# Ethernet_Phy_4_esp32.net
KiCad netlist of a schematic drawn in EAGLE
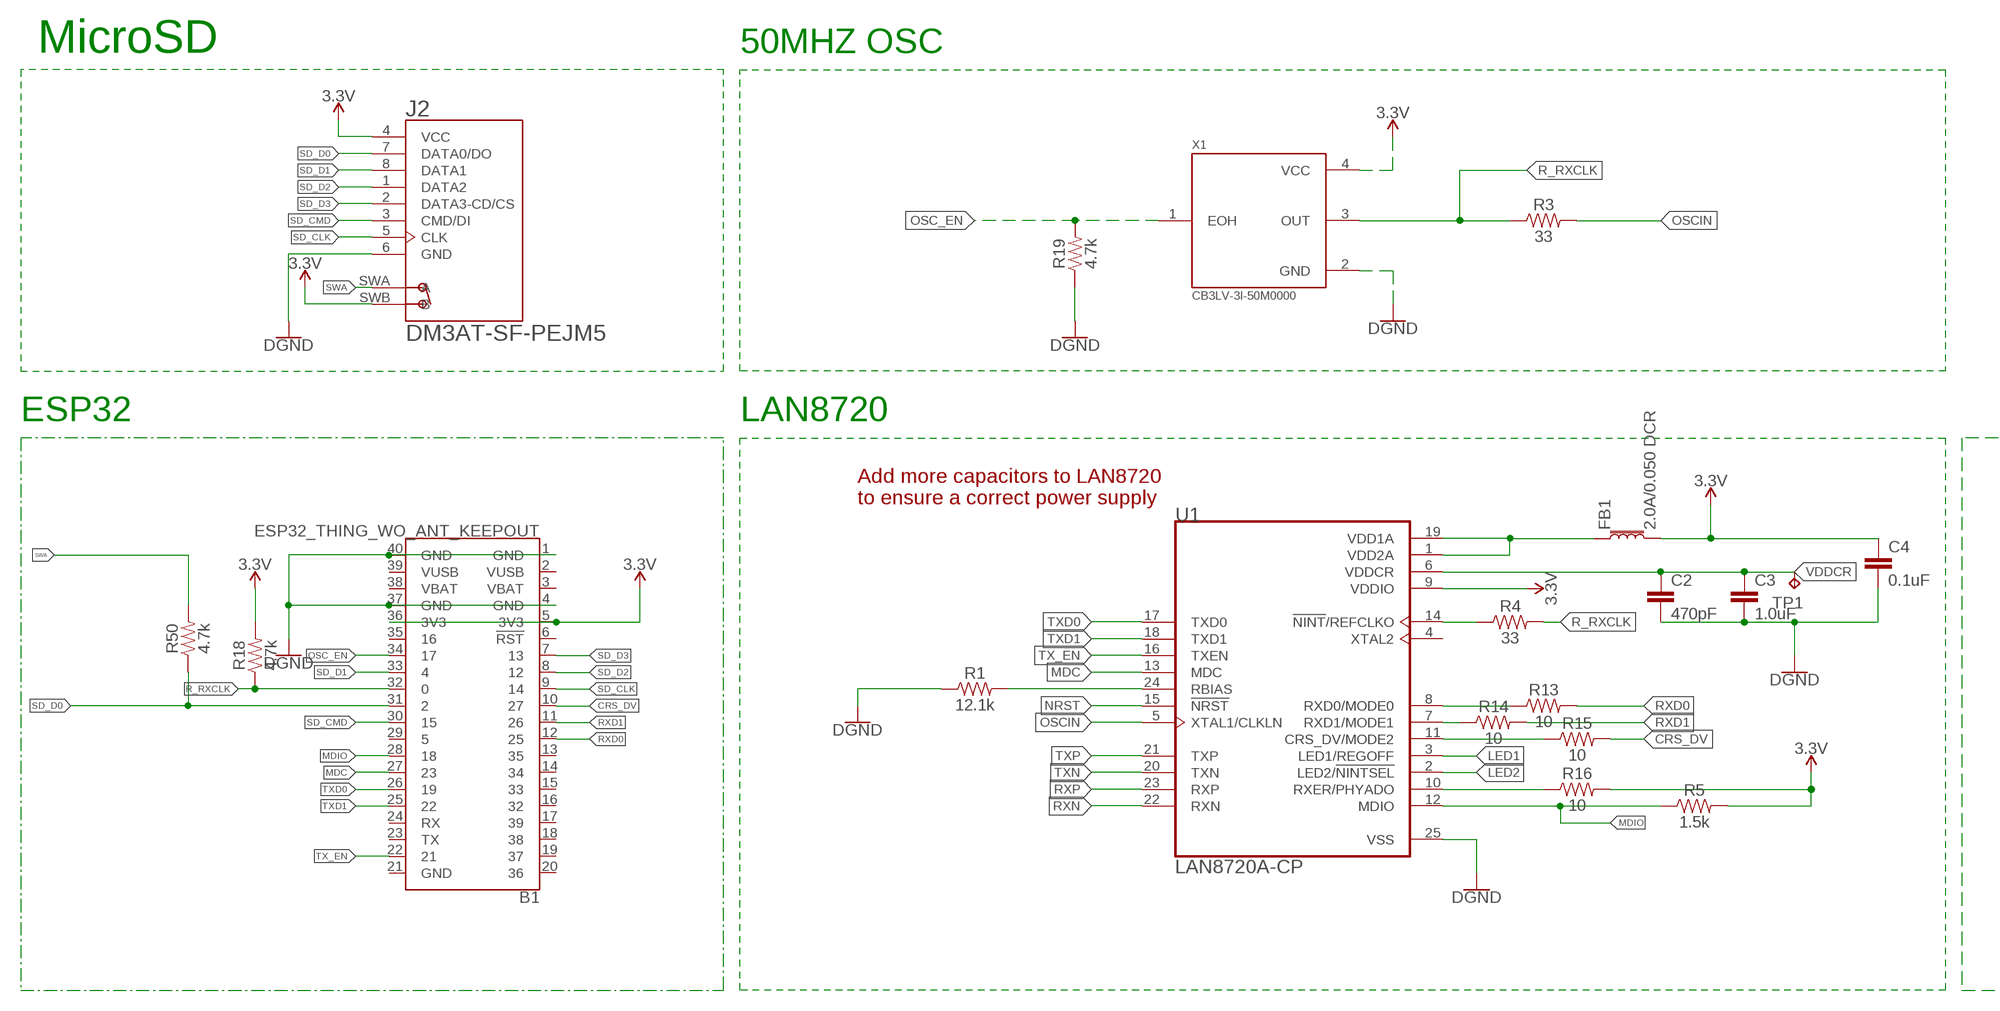
[diagram p0: schematic, sheet 1, part 1 of 2]
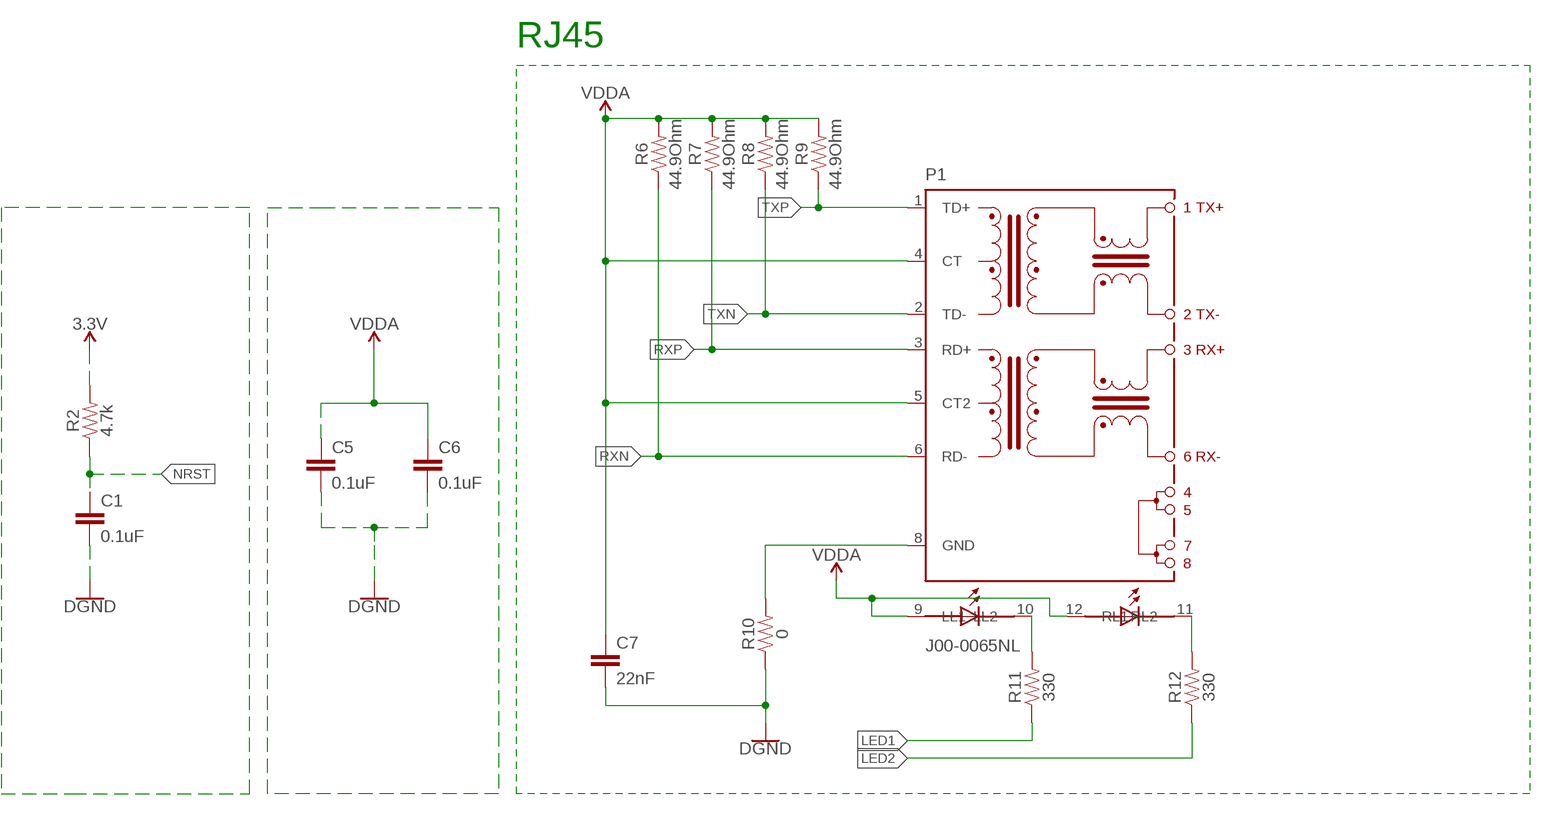
[diagram p1: schematic, sheet 1, part 2 of 2]

(export (version "E")
  (design (tool "Eeschema 10.0.6"))
  (components
    (comp (ref "B1")
      (value "ESP32_THING_WO_ANT_KEEPOUT")
      (footprint "eagle-import:ESP32_THING_NO_ANT")
      (libsource (lib "eagle-import") (part "ESP32_THING_WO_ANT_KEEPOUT"))
    )
    (comp (ref "C1")
      (value "0.1uF")
      (footprint "eagle-import:0603")
      (libsource (lib "eagle-import") (part "0.1UF-0603-100V-10%"))
    )
    (comp (ref "C2")
      (value "470pF")
      (footprint "eagle-import:0603")
      (libsource (lib "eagle-import") (part "470PF-0603-50V-5%"))
    )
    (comp (ref "C3")
      (value "1.0uF")
      (footprint "eagle-import:0603")
      (libsource (lib "eagle-import") (part "1.0UF-0603-16V-10%"))
    )
    (comp (ref "C4")
      (value "0.1uF")
      (footprint "eagle-import:0603")
      (libsource (lib "eagle-import") (part "0.1UF-0603-100V-10%"))
    )
    (comp (ref "C5")
      (value "0.1uF")
      (footprint "eagle-import:0603")
      (libsource (lib "eagle-import") (part "0.1UF-0603-25V-(+80/-20%)"))
    )
    (comp (ref "C6")
      (value "0.1uF")
      (footprint "eagle-import:0603")
      (libsource (lib "eagle-import") (part "0.1UF-0603-25V-(+80/-20%)"))
    )
    (comp (ref "C7")
      (value "22nF")
      (footprint "eagle-import:0603")
      (libsource (lib "eagle-import") (part "22NF/22,000PF-0603-50V-10%"))
    )
    (comp (ref "FB1")
      (value "2.0A/0.050 DCR")
      (footprint "eagle-import:0603")
      (libsource (lib "eagle-import") (part "FERRITE_BEAD-0603"))
    )
    (comp (ref "J2")
      (value "DM3AT-SF-PEJM5")
      (footprint "eagle-import:HRS_DM3AT-SF-PEJM5")
      (fields (field (name "MF") "Hirose"))
      (libsource (lib "eagle-import") (part "DM3AT-SF-PEJM5"))
    )
    (comp (ref "P1")
      (value "J00-0065NL")
      (footprint "eagle-import:PULSE_J00-0065NL")
      (fields (field (name "MF") "Pulse Electronics"))
      (libsource (lib "eagle-import") (part "J00-0065NL"))
    )
    (comp (ref "R1")
      (value "12.1k")
      (footprint "eagle-import:0603")
      (libsource (lib "eagle-import") (part "12.1KOHM-0603-1/10W-1%"))
    )
    (comp (ref "R2")
      (value "4.7k")
      (footprint "eagle-import:0603")
      (libsource (lib "eagle-import") (part "4.7KOHM-0603-1/10W-1%"))
    )
    (comp (ref "R3")
      (value "33")
      (footprint "eagle-import:0603")
      (libsource (lib "eagle-import") (part "33OHM-0603-1/10W-1%"))
    )
    (comp (ref "R4")
      (value "33")
      (footprint "eagle-import:0603")
      (libsource (lib "eagle-import") (part "33OHM-0603-1/10W-1%"))
    )
    (comp (ref "R5")
      (value "1.5k")
      (footprint "eagle-import:0603")
      (libsource (lib "eagle-import") (part "1.5KOHM-0603-1/10W-1%"))
    )
    (comp (ref "R6")
      (value "44.9Ohm")
      (footprint "eagle-import:0603")
      (libsource (lib "eagle-import") (part "43KOHM-0603-1/10W-1%"))
    )
    (comp (ref "R7")
      (value "44.9Ohm")
      (footprint "eagle-import:0603")
      (libsource (lib "eagle-import") (part "43KOHM-0603-1/10W-1%"))
    )
    (comp (ref "R8")
      (value "44.9Ohm")
      (footprint "eagle-import:0603")
      (libsource (lib "eagle-import") (part "43KOHM-0603-1/10W-1%"))
    )
    (comp (ref "R9")
      (value "44.9Ohm")
      (footprint "eagle-import:0603")
      (libsource (lib "eagle-import") (part "43KOHM-0603-1/10W-1%"))
    )
    (comp (ref "R10")
      (value "0")
      (footprint "eagle-import:0603")
      (libsource (lib "eagle-import") (part "0OHM-0603-1/10W-5%"))
    )
    (comp (ref "R11")
      (value "330")
      (footprint "eagle-import:0603")
      (libsource (lib "eagle-import") (part "330OHM-0603-1/10W-1%"))
    )
    (comp (ref "R12")
      (value "330")
      (footprint "eagle-import:0603")
      (libsource (lib "eagle-import") (part "330OHM-0603-1/10W-1%"))
    )
    (comp (ref "R13")
      (value "10")
      (footprint "eagle-import:0603")
      (libsource (lib "eagle-import") (part "10OHM-0603-1/10W-1%"))
    )
    (comp (ref "R14")
      (value "10")
      (footprint "eagle-import:0603")
      (libsource (lib "eagle-import") (part "10OHM-0603-1/10W-1%"))
    )
    (comp (ref "R15")
      (value "10")
      (footprint "eagle-import:0603")
      (libsource (lib "eagle-import") (part "10OHM-0603-1/10W-1%"))
    )
    (comp (ref "R16")
      (value "10")
      (footprint "eagle-import:0603")
      (libsource (lib "eagle-import") (part "10OHM-0603-1/10W-1%"))
    )
    (comp (ref "R18")
      (value "4.7k")
      (footprint "eagle-import:0603")
      (libsource (lib "eagle-import") (part "4.7KOHM-0603-1/10W-1%"))
    )
    (comp (ref "R19")
      (value "4.7k")
      (footprint "eagle-import:0603")
      (libsource (lib "eagle-import") (part "4.7KOHM-0603-1/10W-1%"))
    )
    (comp (ref "R50")
      (value "4.7k")
      (footprint "eagle-import:0603")
      (libsource (lib "eagle-import") (part "4.7KOHM-0603-1/10W-1%"))
    )
    (comp (ref "TP1")
      (value "TPB1,27")
      (footprint "eagle-import:B1,27")
      (libsource (lib "eagle-import") (part "TPB1,27"))
    )
    (comp (ref "U1")
      (value "LAN8720A-CP")
      (footprint "eagle-import:QFN50P400X400X100-25N")
      (fields (field (name "MF") "Microchip"))
      (libsource (lib "eagle-import") (part "LAN8720A-CP"))
    )
    (comp (ref "X1")
      (value "CB3LV-3I-50M0000")
      (footprint "eagle-import:OSCCC700X500X180-4N")
      (fields (field (name "MF") "CTS-Frequency"))
      (libsource (lib "eagle-import") (part "CB3LV-3I-50M0000"))
    )
  )
  (nets
    (net (code "1") (name "3.3V") (class "Default")
      (node (ref "B1") (pin "36") (pinfunction "3V3_36") (pintype "bidirectional"))
      (node (ref "B1") (pin "5") (pinfunction "3V3_5") (pintype "bidirectional"))
      (node (ref "C4") (pin "1") (pinfunction "1_1") (pintype "passive"))
      (node (ref "FB1") (pin "2") (pinfunction "2_2") (pintype "passive"))
      (node (ref "J2") (pin "4") (pinfunction "VCC_4") (pintype "power_in"))
      (node (ref "J2") (pin "SWB") (pinfunction "B_SWB") (pintype "bidirectional"))
      (node (ref "R16") (pin "2") (pinfunction "2_2") (pintype "passive"))
      (node (ref "R18") (pin "2") (pinfunction "2_2") (pintype "passive"))
      (node (ref "R2") (pin "2") (pinfunction "2_2") (pintype "passive"))
      (node (ref "R5") (pin "2") (pinfunction "2_2") (pintype "passive"))
      (node (ref "U1") (pin "9") (pinfunction "VDDIO_9") (pintype "power_in"))
      (node (ref "X1") (pin "4") (pinfunction "VCC_4") (pintype "power_in"))
    )
    (net (code "2") (name "CRS_DV") (class "Default")
      (node (ref "B1") (pin "10") (pinfunction "27_10") (pintype "bidirectional"))
      (node (ref "R15") (pin "2") (pinfunction "2_2") (pintype "passive"))
    )
    (net (code "3") (name "DGND") (class "Default")
      (node (ref "B1") (pin "1") (pinfunction "GND_1") (pintype "bidirectional"))
      (node (ref "B1") (pin "37") (pinfunction "GND_37") (pintype "bidirectional"))
      (node (ref "B1") (pin "4") (pinfunction "GND_4") (pintype "bidirectional"))
      (node (ref "B1") (pin "40") (pinfunction "GND_40") (pintype "bidirectional"))
      (node (ref "C1") (pin "2") (pinfunction "2_2") (pintype "passive"))
      (node (ref "C2") (pin "2") (pinfunction "2_2") (pintype "passive"))
      (node (ref "C3") (pin "2") (pinfunction "2_2") (pintype "passive"))
      (node (ref "C4") (pin "2") (pinfunction "2_2") (pintype "passive"))
      (node (ref "C5") (pin "2") (pinfunction "2_2") (pintype "passive"))
      (node (ref "C6") (pin "2") (pinfunction "2_2") (pintype "passive"))
      (node (ref "C7") (pin "2") (pinfunction "2_2") (pintype "passive"))
      (node (ref "J2") (pin "6") (pinfunction "GND_6") (pintype "power_in"))
      (node (ref "R1") (pin "1") (pinfunction "1_1") (pintype "passive"))
      (node (ref "R10") (pin "1") (pinfunction "1_1") (pintype "passive"))
      (node (ref "R19") (pin "1") (pinfunction "1_1") (pintype "passive"))
      (node (ref "U1") (pin "25") (pinfunction "VSS_25") (pintype "power_in"))
      (node (ref "X1") (pin "2") (pinfunction "GND_2") (pintype "passive"))
    )
    (net (code "4") (name "LED1") (class "Default")
      (node (ref "R11") (pin "1") (pinfunction "1_1") (pintype "passive"))
      (node (ref "U1") (pin "3") (pinfunction "LED1/REGOFF_3") (pintype "bidirectional"))
    )
    (net (code "5") (name "LED2") (class "Default")
      (node (ref "R12") (pin "1") (pinfunction "1_1") (pintype "passive"))
      (node (ref "U1") (pin "2") (pinfunction "LED2/~{NINTSEL}_2") (pintype "bidirectional"))
    )
    (net (code "6") (name "MDC") (class "Default")
      (node (ref "B1") (pin "27") (pinfunction "23_27") (pintype "bidirectional"))
      (node (ref "U1") (pin "13") (pinfunction "MDC_13") (pintype "input"))
    )
    (net (code "7") (name "MDIO") (class "Default")
      (node (ref "B1") (pin "28") (pinfunction "18_28") (pintype "bidirectional"))
      (node (ref "R5") (pin "1") (pinfunction "1_1") (pintype "passive"))
      (node (ref "U1") (pin "12") (pinfunction "MDIO_12") (pintype "bidirectional"))
    )
    (net (code "8") (name "NRST") (class "Default")
      (node (ref "C1") (pin "1") (pinfunction "1_1") (pintype "passive"))
      (node (ref "R2") (pin "1") (pinfunction "1_1") (pintype "passive"))
      (node (ref "U1") (pin "15") (pinfunction "~{NRST}_15") (pintype "input"))
    )
    (net (code "9") (name "Net-(P1-GND)") (class "Default")
      (node (ref "P1") (pin "8") (pinfunction "GND_8") (pintype "passive"))
      (node (ref "R10") (pin "2") (pinfunction "2_2") (pintype "passive"))
    )
    (net (code "10") (name "Net-(P1-LL2)") (class "Default")
      (node (ref "P1") (pin "10") (pinfunction "LL2_10") (pintype "passive"))
      (node (ref "R11") (pin "2") (pinfunction "2_2") (pintype "passive"))
    )
    (net (code "11") (name "Net-(P1-RL2)") (class "Default")
      (node (ref "P1") (pin "11") (pinfunction "RL2_11") (pintype "passive"))
      (node (ref "R12") (pin "2") (pinfunction "2_2") (pintype "passive"))
    )
    (net (code "12") (name "Net-(U1-CRS_DV{slash}MODE2)") (class "Default")
      (node (ref "R15") (pin "1") (pinfunction "1_1") (pintype "passive"))
      (node (ref "U1") (pin "11") (pinfunction "CRS_DV/MODE2_11") (pintype "bidirectional"))
    )
    (net (code "13") (name "Net-(U1-RBIAS)") (class "Default")
      (node (ref "R1") (pin "2") (pinfunction "2_2") (pintype "passive"))
      (node (ref "U1") (pin "24") (pinfunction "RBIAS_24") (pintype "input"))
    )
    (net (code "14") (name "Net-(U1-RXD0{slash}MODE0)") (class "Default")
      (node (ref "R13") (pin "1") (pinfunction "1_1") (pintype "passive"))
      (node (ref "U1") (pin "8") (pinfunction "RXD0/MODE0_8") (pintype "bidirectional"))
    )
    (net (code "15") (name "Net-(U1-RXD1{slash}MODE1)") (class "Default")
      (node (ref "R14") (pin "1") (pinfunction "1_1") (pintype "passive"))
      (node (ref "U1") (pin "7") (pinfunction "RXD1/MODE1_7") (pintype "bidirectional"))
    )
    (net (code "16") (name "Net-(U1-RXER{slash}PHYADO)") (class "Default")
      (node (ref "R16") (pin "1") (pinfunction "1_1") (pintype "passive"))
      (node (ref "U1") (pin "10") (pinfunction "RXER/PHYADO_10") (pintype "bidirectional"))
    )
    (net (code "17") (name "Net-(U1-VDD1A)") (class "Default")
      (node (ref "FB1") (pin "1") (pinfunction "1_1") (pintype "passive"))
      (node (ref "U1") (pin "1") (pinfunction "VDD2A_1") (pintype "power_in"))
      (node (ref "U1") (pin "19") (pinfunction "VDD1A_19") (pintype "power_in"))
    )
    (net (code "18") (name "Net-(U1-~{NINT}{slash}REFCLKO)") (class "Default")
      (node (ref "R4") (pin "1") (pinfunction "1_1") (pintype "passive"))
      (node (ref "U1") (pin "14") (pinfunction "~{NINT}/REFCLKO_14") (pintype "output"))
    )
    (net (code "19") (name "OSCIN") (class "Default")
      (node (ref "R3") (pin "2") (pinfunction "2_2") (pintype "passive"))
      (node (ref "U1") (pin "5") (pinfunction "XTAL1/CLKLN_5") (pintype "input"))
    )
    (net (code "20") (name "OSC_EN") (class "Default")
      (node (ref "B1") (pin "34") (pinfunction "17_34") (pintype "bidirectional"))
      (node (ref "R19") (pin "2") (pinfunction "2_2") (pintype "passive"))
      (node (ref "X1") (pin "1") (pinfunction "EOH_1") (pintype "input"))
    )
    (net (code "21") (name "RXD0") (class "Default")
      (node (ref "B1") (pin "12") (pinfunction "25_12") (pintype "bidirectional"))
      (node (ref "R13") (pin "2") (pinfunction "2_2") (pintype "passive"))
    )
    (net (code "22") (name "RXD1") (class "Default")
      (node (ref "B1") (pin "11") (pinfunction "26_11") (pintype "bidirectional"))
      (node (ref "R14") (pin "2") (pinfunction "2_2") (pintype "passive"))
    )
    (net (code "23") (name "RXN") (class "Default")
      (node (ref "P1") (pin "6") (pinfunction "RD-_6") (pintype "input"))
      (node (ref "R6") (pin "1") (pinfunction "1_1") (pintype "passive"))
      (node (ref "U1") (pin "22") (pinfunction "RXN_22") (pintype "bidirectional"))
    )
    (net (code "24") (name "RXP") (class "Default")
      (node (ref "P1") (pin "3") (pinfunction "RD+_3") (pintype "input"))
      (node (ref "R7") (pin "1") (pinfunction "1_1") (pintype "passive"))
      (node (ref "U1") (pin "23") (pinfunction "RXP_23") (pintype "bidirectional"))
    )
    (net (code "25") (name "R_RXCLK") (class "Default")
      (node (ref "B1") (pin "32") (pinfunction "0_32") (pintype "bidirectional"))
      (node (ref "R18") (pin "1") (pinfunction "1_1") (pintype "passive"))
      (node (ref "R3") (pin "1") (pinfunction "1_1") (pintype "passive"))
      (node (ref "R4") (pin "2") (pinfunction "2_2") (pintype "passive"))
      (node (ref "X1") (pin "3") (pinfunction "OUT_3") (pintype "output"))
    )
    (net (code "26") (name "SD_CLK") (class "Default")
      (node (ref "B1") (pin "9") (pinfunction "14_9") (pintype "bidirectional"))
      (node (ref "J2") (pin "5") (pinfunction "CLK_5") (pintype "bidirectional"))
    )
    (net (code "27") (name "SD_CMD") (class "Default")
      (node (ref "B1") (pin "30") (pinfunction "15_30") (pintype "bidirectional"))
      (node (ref "J2") (pin "3") (pinfunction "CMD/DI_3") (pintype "bidirectional"))
    )
    (net (code "28") (name "SD_D0") (class "Default")
      (node (ref "B1") (pin "31") (pinfunction "2_31") (pintype "bidirectional"))
      (node (ref "J2") (pin "7") (pinfunction "DATA0/DO_7") (pintype "bidirectional"))
      (node (ref "R50") (pin "1") (pinfunction "1_1") (pintype "passive"))
    )
    (net (code "29") (name "SD_D1") (class "Default")
      (node (ref "B1") (pin "33") (pinfunction "4_33") (pintype "bidirectional"))
      (node (ref "J2") (pin "8") (pinfunction "DATA1_8") (pintype "bidirectional"))
    )
    (net (code "30") (name "SD_D2") (class "Default")
      (node (ref "B1") (pin "8") (pinfunction "12_8") (pintype "bidirectional"))
      (node (ref "J2") (pin "1") (pinfunction "DATA2_1") (pintype "bidirectional"))
    )
    (net (code "31") (name "SD_D3") (class "Default")
      (node (ref "B1") (pin "7") (pinfunction "13_7") (pintype "bidirectional"))
      (node (ref "J2") (pin "2") (pinfunction "DATA3-CD/CS_2") (pintype "bidirectional"))
    )
    (net (code "32") (name "SWA") (class "Default")
      (node (ref "J2") (pin "SWA") (pinfunction "A_SWA") (pintype "bidirectional"))
      (node (ref "R50") (pin "2") (pinfunction "2_2") (pintype "passive"))
    )
    (net (code "33") (name "TXD0") (class "Default")
      (node (ref "B1") (pin "26") (pinfunction "19_26") (pintype "bidirectional"))
      (node (ref "U1") (pin "17") (pinfunction "TXD0_17") (pintype "input"))
    )
    (net (code "34") (name "TXD1") (class "Default")
      (node (ref "B1") (pin "25") (pinfunction "22_25") (pintype "bidirectional"))
      (node (ref "U1") (pin "18") (pinfunction "TXD1_18") (pintype "input"))
    )
    (net (code "35") (name "TXN") (class "Default")
      (node (ref "P1") (pin "2") (pinfunction "TD-_2") (pintype "input"))
      (node (ref "R8") (pin "1") (pinfunction "1_1") (pintype "passive"))
      (node (ref "U1") (pin "20") (pinfunction "TXN_20") (pintype "bidirectional"))
    )
    (net (code "36") (name "TXP") (class "Default")
      (node (ref "P1") (pin "1") (pinfunction "TD+_1") (pintype "input"))
      (node (ref "R9") (pin "1") (pinfunction "1_1") (pintype "passive"))
      (node (ref "U1") (pin "21") (pinfunction "TXP_21") (pintype "bidirectional"))
    )
    (net (code "37") (name "TX_EN") (class "Default")
      (node (ref "B1") (pin "22") (pinfunction "21_22") (pintype "bidirectional"))
      (node (ref "U1") (pin "16") (pinfunction "TXEN_16") (pintype "input"))
    )
    (net (code "38") (name "VDDA") (class "Default")
      (node (ref "C5") (pin "1") (pinfunction "1_1") (pintype "passive"))
      (node (ref "C6") (pin "1") (pinfunction "1_1") (pintype "passive"))
      (node (ref "C7") (pin "1") (pinfunction "1_1") (pintype "passive"))
      (node (ref "P1") (pin "12") (pinfunction "RL1_12") (pintype "passive"))
      (node (ref "P1") (pin "4") (pinfunction "CT_4") (pintype "input"))
      (node (ref "P1") (pin "5") (pinfunction "CT2_5") (pintype "input"))
      (node (ref "P1") (pin "9") (pinfunction "LL1_9") (pintype "passive"))
      (node (ref "R6") (pin "2") (pinfunction "2_2") (pintype "passive"))
      (node (ref "R7") (pin "2") (pinfunction "2_2") (pintype "passive"))
      (node (ref "R8") (pin "2") (pinfunction "2_2") (pintype "passive"))
      (node (ref "R9") (pin "2") (pinfunction "2_2") (pintype "passive"))
    )
    (net (code "39") (name "VDDCR") (class "Default")
      (node (ref "C2") (pin "1") (pinfunction "1_1") (pintype "passive"))
      (node (ref "C3") (pin "1") (pinfunction "1_1") (pintype "passive"))
      (node (ref "TP1") (pin "TP") (pinfunction "TP_TP") (pintype "input"))
      (node (ref "U1") (pin "6") (pinfunction "VDDCR_6") (pintype "power_in"))
    )
    (net (code "40") (name "unconnected-(B1-5-Pad29)") (class "Default")
      (node (ref "B1") (pin "29") (pinfunction "5_29") (pintype "bidirectional"))
    )
    (net (code "41") (name "unconnected-(B1-16-Pad35)") (class "Default")
      (node (ref "B1") (pin "35") (pinfunction "16_35") (pintype "bidirectional"))
    )
    (net (code "42") (name "unconnected-(B1-32-Pad16)") (class "Default")
      (node (ref "B1") (pin "16") (pinfunction "32_16") (pintype "bidirectional"))
    )
    (net (code "43") (name "unconnected-(B1-33-Pad15)") (class "Default")
      (node (ref "B1") (pin "15") (pinfunction "33_15") (pintype "bidirectional"))
    )
    (net (code "44") (name "unconnected-(B1-34-Pad14)") (class "Default")
      (node (ref "B1") (pin "14") (pinfunction "34_14") (pintype "bidirectional"))
    )
    (net (code "45") (name "unconnected-(B1-35-Pad13)") (class "Default")
      (node (ref "B1") (pin "13") (pinfunction "35_13") (pintype "bidirectional"))
    )
    (net (code "46") (name "unconnected-(B1-36-Pad20)") (class "Default")
      (node (ref "B1") (pin "20") (pinfunction "36_20") (pintype "bidirectional"))
    )
    (net (code "47") (name "unconnected-(B1-37-Pad19)") (class "Default")
      (node (ref "B1") (pin "19") (pinfunction "37_19") (pintype "bidirectional"))
    )
    (net (code "48") (name "unconnected-(B1-38-Pad18)") (class "Default")
      (node (ref "B1") (pin "18") (pinfunction "38_18") (pintype "bidirectional"))
    )
    (net (code "49") (name "unconnected-(B1-39-Pad17)") (class "Default")
      (node (ref "B1") (pin "17") (pinfunction "39_17") (pintype "bidirectional"))
    )
    (net (code "50") (name "unconnected-(B1-GND-Pad21)") (class "Default")
      (node (ref "B1") (pin "21") (pinfunction "GND_21") (pintype "bidirectional"))
    )
    (net (code "51") (name "unconnected-(B1-RX-Pad24)") (class "Default")
      (node (ref "B1") (pin "24") (pinfunction "RX_24") (pintype "bidirectional"))
    )
    (net (code "52") (name "unconnected-(B1-TX-Pad23)") (class "Default")
      (node (ref "B1") (pin "23") (pinfunction "TX_23") (pintype "bidirectional"))
    )
    (net (code "53") (name "unconnected-(B1-VBAT-Pad3)") (class "Default")
      (node (ref "B1") (pin "3") (pinfunction "VBAT_3") (pintype "bidirectional"))
    )
    (net (code "54") (name "unconnected-(B1-VBAT-Pad38)") (class "Default")
      (node (ref "B1") (pin "38") (pinfunction "VBAT_38") (pintype "bidirectional"))
    )
    (net (code "55") (name "unconnected-(B1-VUSB-Pad2)") (class "Default")
      (node (ref "B1") (pin "2") (pinfunction "VUSB_2") (pintype "bidirectional"))
    )
    (net (code "56") (name "unconnected-(B1-VUSB-Pad39)") (class "Default")
      (node (ref "B1") (pin "39") (pinfunction "VUSB_39") (pintype "bidirectional"))
    )
    (net (code "57") (name "unconnected-(B1-~{RST}-Pad6)") (class "Default")
      (node (ref "B1") (pin "6") (pinfunction "~{RST}_6") (pintype "bidirectional"))
    )
    (net (code "58") (name "unconnected-(U1-XTAL2-Pad4)") (class "Default")
      (node (ref "U1") (pin "4") (pinfunction "XTAL2_4") (pintype "output"))
    )
  )
)
